# BeaglePhone_Rev1_SCH.net
KiCad netlist of a schematic drawn in Altium Designer
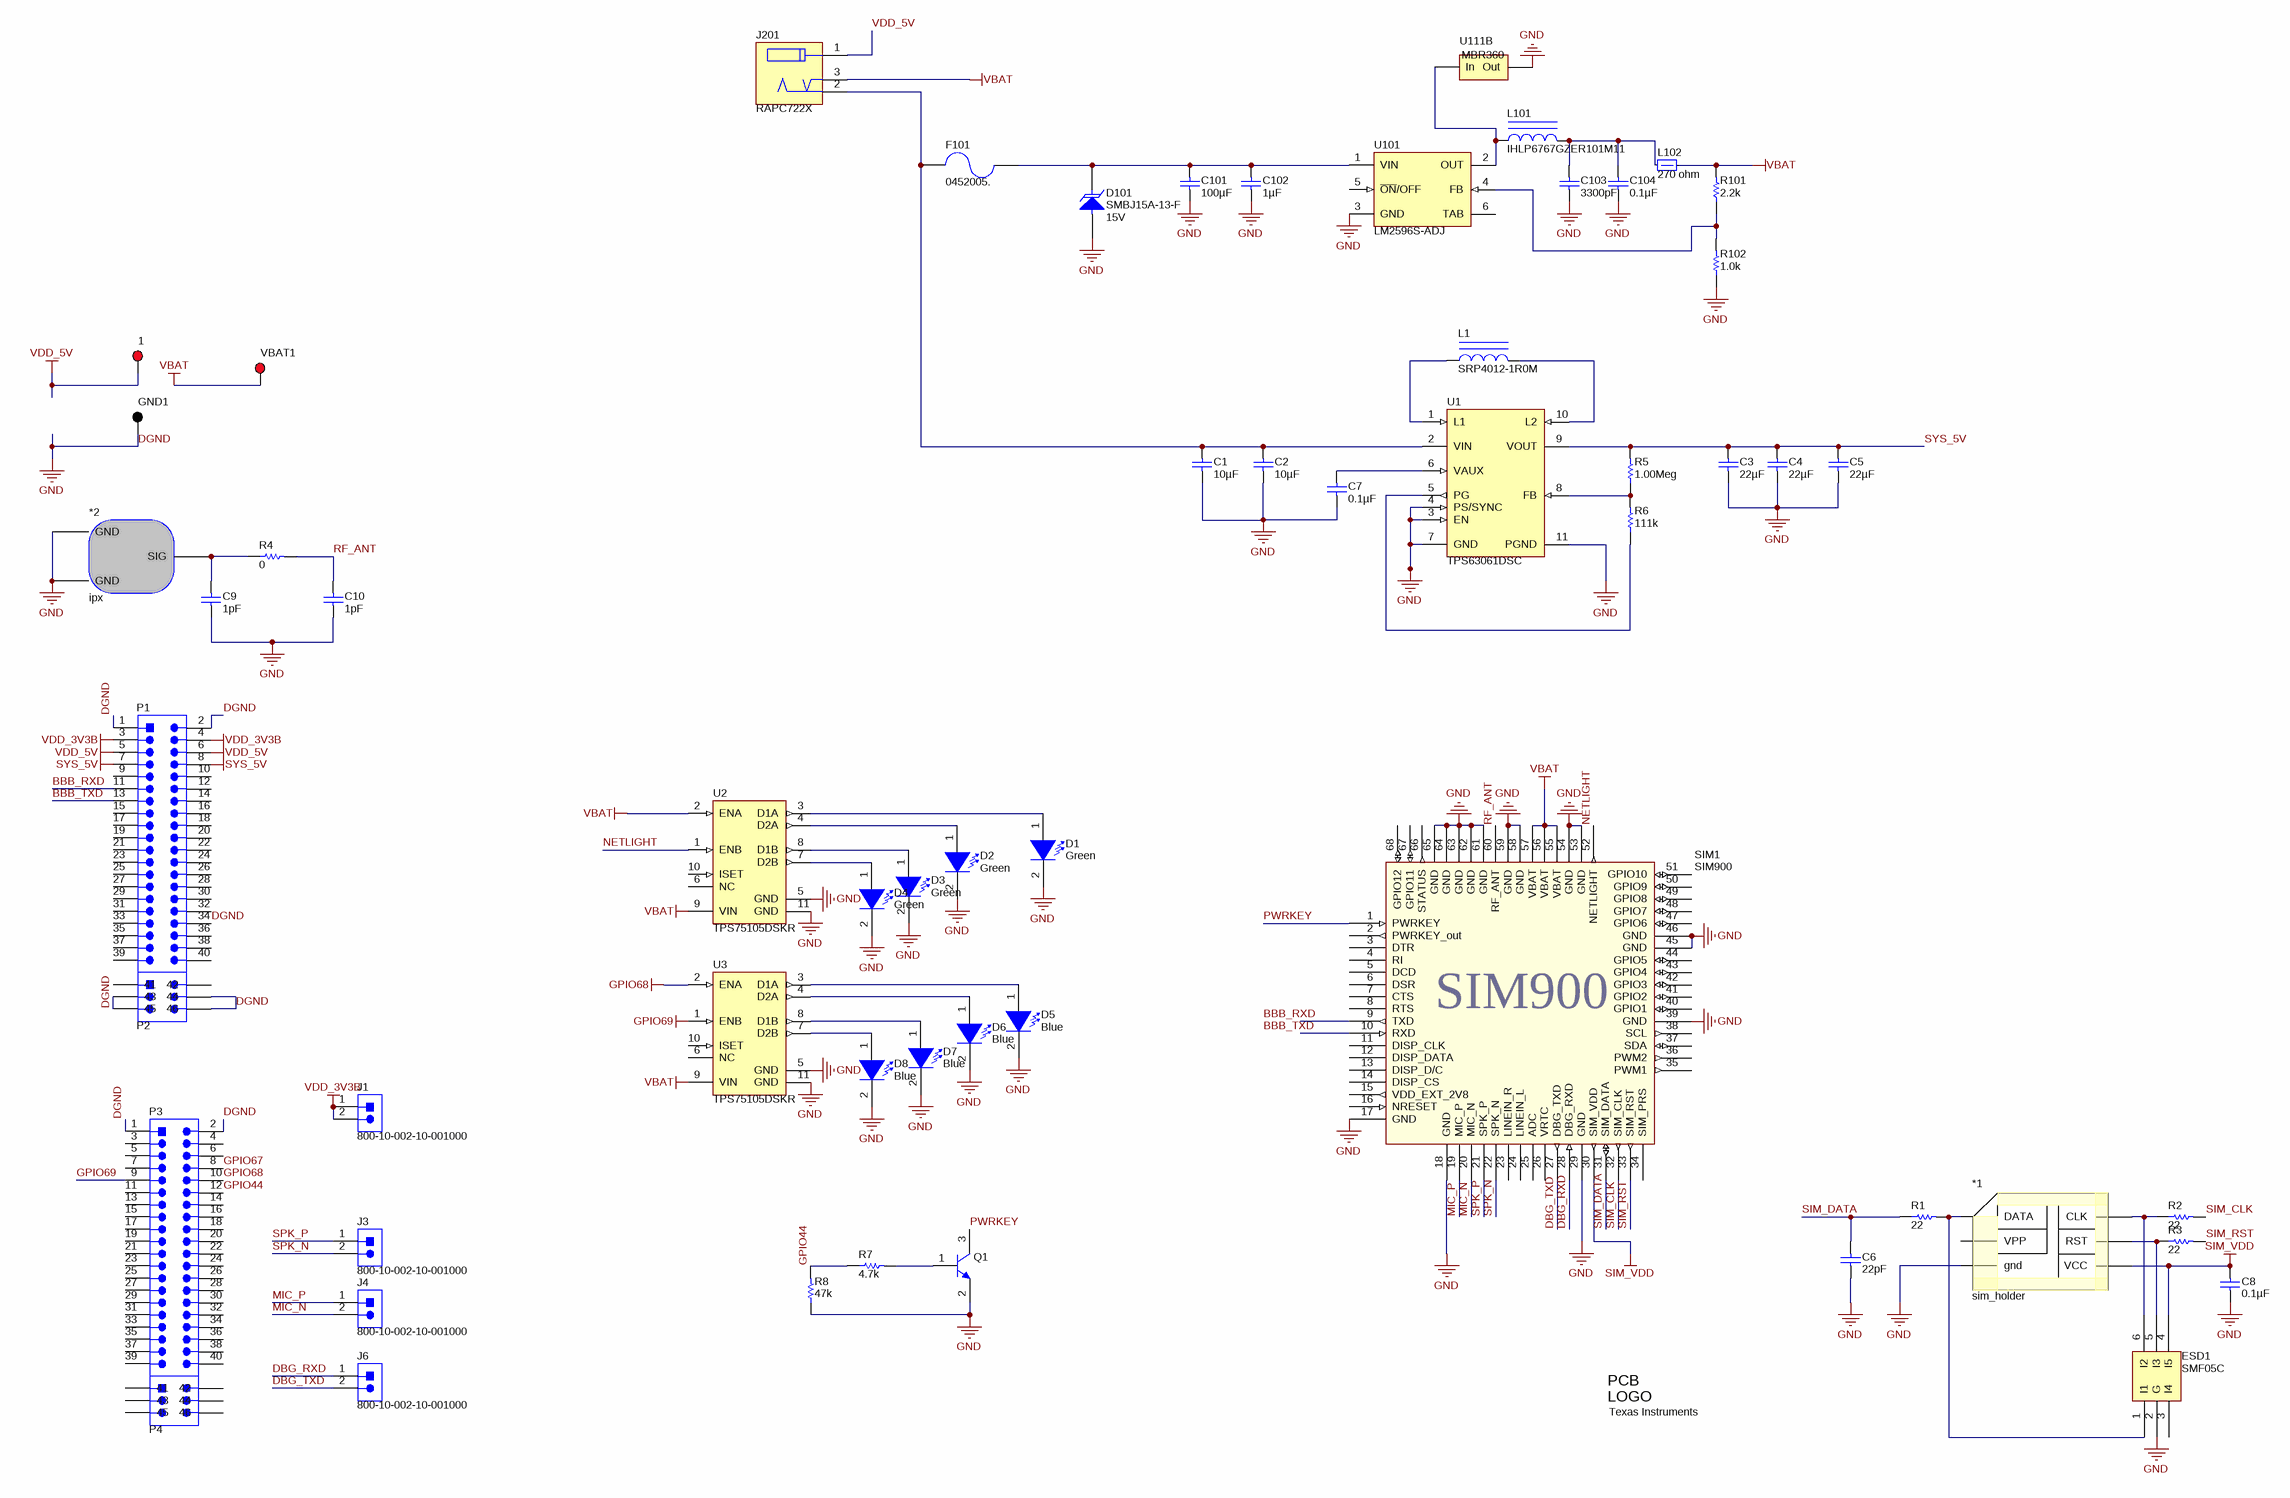
[diagram p0: BeaglePhone_Rev1_SCH.SchDoc]

(export (version "E")
  (design (tool "Eeschema 10.0.6"))
  (components
    (comp (ref "*1")
      (value "sim_holder")
      (footprint "SIM_socket")
      (libsource (lib "sim_holder") (part "sim_holder"))
    )
    (comp (ref "*2") (value "ipx") (footprint "IPX_U.FL") (libsource (lib "u.fl_IPX_connector") (part "ipx")))
    (comp (ref "1")
      (value "5005")
      (footprint "Keystone5005")
      (description "Test Point, TH, Compact, Red")
      (fields (field (name "MANUFACTURER") "Keystone") (field (name "DIGIKEYPARTNUMBER") "5005K-ND"))
      (libsource (lib "TemplateSCHLib") (part "5005"))
    )
    (comp (ref "C1")
      (value "C1608X5R1A106M")
      (footprint "0603")
      (description "CAP, CERM, 10uF, 10V, +/-20%, X5R, 0603")
      (fields (field (name "VALUEDISPLAYED") "10µF") (field (name "MANUFACTURER") "TDK"))
      (libsource (lib "Capacitor_Ceramic") (part "C1608X5R1A106M"))
    )
    (comp (ref "C2")
      (value "C1608X5R1A106M")
      (footprint "0603")
      (description "CAP, CERM, 10uF, 10V, +/-20%, X5R, 0603")
      (fields (field (name "VALUEDISPLAYED") "10µF") (field (name "MANUFACTURER") "TDK"))
      (libsource (lib "Capacitor_Ceramic") (part "C1608X5R1A106M"))
    )
    (comp (ref "C3")
      (value "C1608X5R0G226M080AA")
      (footprint "0603")
      (description "CAP, CERM, 22uF, 4V, +/-20%, X5R, 0603")
      (fields (field (name "VALUEDISPLAYED") "22µF") (field (name "MANUFACTURER") "TDK"))
      (libsource (lib "Capacitor_Ceramic") (part "C1608X5R0G226M080AA"))
    )
    (comp (ref "C4")
      (value "C1608X5R0G226M080AA")
      (footprint "0603")
      (description "CAP, CERM, 22uF, 4V, +/-20%, X5R, 0603")
      (fields (field (name "VALUEDISPLAYED") "22µF") (field (name "MANUFACTURER") "TDK"))
      (libsource (lib "Capacitor_Ceramic") (part "C1608X5R0G226M080AA"))
    )
    (comp (ref "C5")
      (value "C1608X5R0G226M080AA")
      (footprint "0603")
      (description "CAP, CERM, 22uF, 4V, +/-20%, X5R, 0603")
      (fields (field (name "VALUEDISPLAYED") "22µF") (field (name "MANUFACTURER") "TDK"))
      (libsource (lib "Capacitor_Ceramic") (part "C1608X5R0G226M080AA"))
    )
    (comp (ref "C6")
      (value "GRM1885C2A220JA01D")
      (footprint "0603")
      (description "CAP, CERM, 22pF, 100V, +/-5%, C0G/NP0, 0603")
      (fields (field (name "VALUEDISPLAYED") "22pF") (field (name "MANUFACTURER") "MuRata"))
      (libsource (lib "Capacitor_Ceramic") (part "GRM1885C2A220JA01D"))
    )
    (comp (ref "C7")
      (value "C0603X104K3RACTU")
      (footprint "0603")
      (description "CAP, CERM, 0.1uF, 25V, +/-10%, X7R, 0603")
      (fields (field (name "VALUEDISPLAYED") "0.1µF") (field (name "MANUFACTURER") "Kemet"))
      (libsource (lib "Capacitor_Ceramic") (part "C0603X104K3RACTU"))
    )
    (comp (ref "C8")
      (value "06035C104KAT2A")
      (footprint "0603")
      (description "CAP, CERM, 0.1 µF, 50 V, +/- 10%, X7R, 0603")
      (fields (field (name "VALUEDISPLAYED") "0.1µF") (field (name "MANUFACTURER") "AVX"))
      (libsource (lib "Capacitor_Ceramic") (part "06035C104KAT2A"))
    )
    (comp (ref "C9")
      (value "C0603C109C5GACTU")
      (footprint "0603")
      (description "CAP, CERM, 1pF, 50V, +/-25%, C0G/NP0, 0603")
      (fields (field (name "VALUEDISPLAYED") "1pF") (field (name "MANUFACTURER") "Kemet"))
      (libsource (lib "Capacitor_Ceramic") (part "C0603C109C5GACTU"))
    )
    (comp (ref "C10")
      (value "C0603C109C5GACTU")
      (footprint "0603")
      (description "CAP, CERM, 1pF, 50V, +/-25%, C0G/NP0, 0603")
      (fields (field (name "VALUEDISPLAYED") "1pF") (field (name "MANUFACTURER") "Kemet"))
      (libsource (lib "Capacitor_Ceramic") (part "C0603C109C5GACTU"))
    )
    (comp (ref "C101")
      (value "GRM31CR60J107ME39L")
      (footprint "1206")
      (description "CAP, CERM, 100uF, 6.3V, +/-20%, X5R, 1206")
      (fields (field (name "VALUEDISPLAYED") "100µF") (field (name "MANUFACTURER") "MuRata"))
      (libsource (lib "Capacitor_Ceramic") (part "GRM31CR60J107ME39L"))
    )
    (comp (ref "C102")
      (value "GRM188R61A105KA61D")
      (footprint "0603")
      (description "CAP, CERM, 1uF, 10V, +/-10%, X5R, 0603")
      (fields (field (name "VALUEDISPLAYED") "1µF") (field (name "MANUFACTURER") "MuRata"))
      (libsource (lib "Capacitor_Ceramic") (part "GRM188R61A105KA61D"))
    )
    (comp (ref "C103")
      (value "GRM188R71H332KA01D")
      (footprint "0603")
      (description "CAP, CERM, 3300pF, 50V, +/-10%, X7R, 0603")
      (fields (field (name "VALUEDISPLAYED") "3300pF") (field (name "MANUFACTURER") "MuRata"))
      (libsource (lib "Capacitor_Ceramic") (part "GRM188R71H332KA01D"))
    )
    (comp (ref "C104")
      (value "C0603X104K4RACTU")
      (footprint "0603")
      (description "CAP, CERM, 0.1uF, 16V, +/-10%, X7R, 0603")
      (fields (field (name "VALUEDISPLAYED") "0.1µF") (field (name "MANUFACTURER") "Kemet"))
      (libsource (lib "Capacitor_Ceramic") (part "C0603X104K4RACTU"))
    )
    (comp (ref "D1")
      (value "Green")
      (footprint "LG L29K_GREEN")
      (description "LED, Green, SMD")
      (fields (field (name "MANUFACTURER") "OSRAM") (field (name "PARTNUMBER") "LG L29K-G2J1-24-Z"))
      (libsource (lib "LED") (part "LG L29K-G2J1-24-Z"))
    )
    (comp (ref "D2")
      (value "Green")
      (footprint "LG L29K_GREEN")
      (description "LED, Green, SMD")
      (fields (field (name "MANUFACTURER") "OSRAM") (field (name "PARTNUMBER") "LG L29K-G2J1-24-Z"))
      (libsource (lib "LED") (part "LG L29K-G2J1-24-Z"))
    )
    (comp (ref "D3")
      (value "Green")
      (footprint "LG L29K_GREEN")
      (description "LED, Green, SMD")
      (fields (field (name "MANUFACTURER") "OSRAM") (field (name "PARTNUMBER") "LG L29K-G2J1-24-Z"))
      (libsource (lib "LED") (part "LG L29K-G2J1-24-Z"))
    )
    (comp (ref "D4")
      (value "Green")
      (footprint "LG L29K_GREEN")
      (description "LED, Green, SMD")
      (fields (field (name "MANUFACTURER") "OSRAM") (field (name "PARTNUMBER") "LG L29K-G2J1-24-Z"))
      (libsource (lib "LED") (part "LG L29K-G2J1-24-Z"))
    )
    (comp (ref "D5")
      (value "Blue")
      (footprint "LB Q39G_BLUE")
      (description "LED, Blue, SMD")
      (fields (field (name "MANUFACTURER") "OSRAM") (field (name "PARTNUMBER") "LB Q39G-L2N2-35-1"))
      (libsource (lib "LED") (part "LB Q39G-L2N2-35-1"))
    )
    (comp (ref "D6")
      (value "Blue")
      (footprint "LB Q39G_BLUE")
      (description "LED, Blue, SMD")
      (fields (field (name "MANUFACTURER") "OSRAM") (field (name "PARTNUMBER") "LB Q39G-L2N2-35-1"))
      (libsource (lib "LED") (part "LB Q39G-L2N2-35-1"))
    )
    (comp (ref "D7")
      (value "Blue")
      (footprint "LB Q39G_BLUE")
      (description "LED, Blue, SMD")
      (fields (field (name "MANUFACTURER") "OSRAM") (field (name "PARTNUMBER") "LB Q39G-L2N2-35-1"))
      (libsource (lib "LED") (part "LB Q39G-L2N2-35-1"))
    )
    (comp (ref "D8")
      (value "Blue")
      (footprint "LB Q39G_BLUE")
      (description "LED, Blue, SMD")
      (fields (field (name "MANUFACTURER") "OSRAM") (field (name "PARTNUMBER") "LB Q39G-L2N2-35-1"))
      (libsource (lib "LED") (part "LB Q39G-L2N2-35-1"))
    )
    (comp (ref "D101")
      (value "SMBJ15A-13-F")
      (footprint "SMB")
      (description "Diode, TVS, Uni, 15V, 600W, SMB")
      (fields (field (name "ALTIUM_VALUE") "15V") (field (name "MANUFACTURER") "Diodes Inc."))
      (libsource (lib "ZenerDiodes") (part "SMBJ15A-13-F"))
    )
    (comp (ref "ESD1") (value "SMF05C") (footprint "6pin") (libsource (lib "SMF05C") (part "SMF05C")))
    (comp (ref "F101")
      (value "0452005.")
      (footprint "SloBlo452")
      (description "Fuse, 5A, 125V, SMD")
      (fields (field (name "MANUFACTURER") "Littelfuse"))
      (libsource (lib "Fuse") (part "0452005."))
    )
    (comp (ref "GND1")
      (value "5006")
      (footprint "Keystone5006")
      (description "Test Point, TH, Compact, Black")
      (fields (field (name "MANUFACTURER") "Keystone") (field (name "DIGIKEYPARTNUMBER") "5006K-ND"))
      (libsource (lib "TemplateSCHLib") (part "5006"))
    )
    (comp (ref "J1")
      (value "800-10-002-10-001000")
      (footprint "Mill-Max_800-10-002-10-001000")
      (description "Header, 2x1, 100mil, SMT")
      (fields (field (name "MANUFACTURER") "Mill-Max"))
      (libsource (lib "Connectors") (part "800-10-002-10-001000"))
    )
    (comp (ref "J3")
      (value "800-10-002-10-001000")
      (footprint "Mill-Max_800-10-002-10-001000")
      (description "Header, 2x1, 100mil, SMT")
      (fields (field (name "MANUFACTURER") "Mill-Max"))
      (libsource (lib "Connectors") (part "800-10-002-10-001000"))
    )
    (comp (ref "J4")
      (value "800-10-002-10-001000")
      (footprint "Mill-Max_800-10-002-10-001000")
      (description "Header, 2x1, 100mil, SMT")
      (fields (field (name "MANUFACTURER") "Mill-Max"))
      (libsource (lib "Connectors") (part "800-10-002-10-001000"))
    )
    (comp (ref "J6")
      (value "800-10-002-10-001000")
      (footprint "Mill-Max_800-10-002-10-001000")
      (description "Header, 2x1, 100mil, SMT")
      (fields (field (name "MANUFACTURER") "Mill-Max"))
      (libsource (lib "Connectors") (part "800-10-002-10-001000"))
    )
    (comp (ref "J201")
      (value "RAPC722X")
      (footprint "CONN_RAPC722X")
      (description "Power Jack, mini, 2.1mm OD, R/A, TH")
      (fields (field (name "MANUFACTURER") "Switchcraft"))
      (libsource (lib "Connectors") (part "RAPC722X"))
    )
    (comp (ref "L1")
      (value "SRP4012-1R0M")
      (footprint "SRP4012")
      (description "Inductor, Flat Wire, Powdered Iron, 1uH, 4.8A, 0.0336 ohm, SMD")
      (fields (field (name "MANUFACTURER") "Bourns"))
      (libsource (lib "Inductor_Bourns") (part "SRP4012-1R0M"))
    )
    (comp (ref "L101")
      (value "IHLP6767GZER101M11")
      (footprint "IHLP-6767GZ-11")
      (description "Inductor, Shielded, Powdered Iron, 100uH, 4A, 0.11 ohm, SMD")
      (fields (field (name "MANUFACTURER") "Vishay-Dale"))
      (libsource (lib "Inductor_Vishay") (part "IHLP6767GZER101M11"))
    )
    (comp (ref "L102")
      (value "270 ohm")
      (footprint "2220")
      (description "Ferrite Bead, 270 ohm @ 100MHz, 4A, 2220")
      (fields
        (field (name "PARTNUMBER") "HI2220P271R-10")
        (field (name "MANUFACTURER") "Laird-Signal Integrity Products")
      )
      (libsource (lib "FerriteBead") (part "HI2220P271R-10"))
    )
    (comp (ref "Logo1")
      (value "Texas Instruments")
      (footprint "TI_Symbol_Overlay_Small")
      (description "Texas Instrument Corporate Signature")
      (libsource (lib "Logos") (part "TI_Logo"))
    )
    (comp (ref "P1")
      (value "Comment")
      (footprint "TSW-120-07-G-D")
      (description "Header, 100mil, 20x2, Gold, TH")
      (fields (field (name "PARTNUMBER") "TSW-120-07-G-D") (field (name "MANUFACTURER") "Samtec"))
      (libsource (lib "Connectors") (part "TSW-120-07-G-D"))
    )
    (comp (ref "P2")
      (value "Comment")
      (footprint "SULLINS_PEC03DAAN")
      (description "Header, 100mil, 3x2, Tin, TH")
      (fields
        (field (name "PARTNUMBER") "PEC03DAAN")
        (field (name "MANUFACTURER") "Sullins Connector Solutions")
      )
      (libsource (lib "Connectors") (part "PEC03DAAN"))
    )
    (comp (ref "P3")
      (value "Comment")
      (footprint "TSW-120-07-G-D")
      (description "Header, 100mil, 20x2, Gold, TH")
      (fields (field (name "PARTNUMBER") "TSW-120-07-G-D") (field (name "MANUFACTURER") "Samtec"))
      (libsource (lib "Connectors") (part "TSW-120-07-G-D"))
    )
    (comp (ref "P4")
      (value "Comment")
      (footprint "SULLINS_PEC03DAAN")
      (description "Header, 100mil, 3x2, Tin, TH")
      (fields
        (field (name "PARTNUMBER") "PEC03DAAN")
        (field (name "MANUFACTURER") "Sullins Connector Solutions")
      )
      (libsource (lib "Connectors") (part "PEC03DAAN"))
    )
    (comp (ref "Q1")
      (value "MMBT2222LT1G")
      (footprint "SOT-23")
      (description "Transistor, NPN, 30V, 0.6A, SOT-23")
      (fields (field (name "MANUFACTURER") "ON Semiconductor"))
      (libsource (lib "Bipolar_Transistor") (part "MMBT2222LT1G, ON Semiconductor"))
    )
    (comp (ref "R1")
      (value "22")
      (footprint "0603")
      (description "RES, 22 ohm, 5%, 0.1W, 0603")
      (fields (field (name "PARTNUMBER") "CRCW060322R0JNEA") (field (name "MANUFACTURER") "Vishay-Dale"))
      (libsource (lib "Resistor_0603") (part "CRCW060322R0JNEA"))
    )
    (comp (ref "R2")
      (value "22")
      (footprint "0603")
      (description "RES, 22 ohm, 5%, 0.1W, 0603")
      (fields (field (name "PARTNUMBER") "CRCW060322R0JNEA") (field (name "MANUFACTURER") "Vishay-Dale"))
      (libsource (lib "Resistor_0603") (part "CRCW060322R0JNEA"))
    )
    (comp (ref "R3")
      (value "22")
      (footprint "0603")
      (description "RES, 22 ohm, 5%, 0.1W, 0603")
      (fields (field (name "PARTNUMBER") "CRCW060322R0JNEA") (field (name "MANUFACTURER") "Vishay-Dale"))
      (libsource (lib "Resistor_0603") (part "CRCW060322R0JNEA"))
    )
    (comp (ref "R4")
      (value "0")
      (footprint "0805_HV")
      (description "RES, 0 ohm, 5%, 0.333W, 0805")
      (fields (field (name "PARTNUMBER") "CRCW08050000Z0EAHP") (field (name "MANUFACTURER") "Vishay-Dale"))
      (libsource (lib "Resistor_0805") (part "CRCW08050000Z0EAHP"))
    )
    (comp (ref "R5")
      (value "1.00Meg")
      (footprint "0603")
      (description "RES, 1.00Meg ohm, 1%, 0.1W, 0603")
      (fields (field (name "PARTNUMBER") "CRCW06031M00FKEA") (field (name "MANUFACTURER") "Vishay-Dale"))
      (libsource (lib "Resistor_0603") (part "CRCW06031M00FKEA"))
    )
    (comp (ref "R6")
      (value "111k")
      (footprint "0603")
      (description "RES, 111k ohm, 0.1%, 0.1W, 0603")
      (fields (field (name "PARTNUMBER") "RT0603BRD07111KL") (field (name "MANUFACTURER") "Yageo America"))
      (libsource (lib "Resistor_0603") (part "RT0603BRD07111KL"))
    )
    (comp (ref "R7")
      (value "CRCW04024K70JNED")
      (footprint "0402")
      (description "RES, 4.7 k, 5%, 0.063 W, 0402")
      (fields (field (name "VALUEDISPLAYED") "4.7k") (field (name "MANUFACTURER") "Vishay-Dale"))
      (libsource (lib "Resistor_0402") (part "CRCW04024K70JNED"))
    )
    (comp (ref "R8")
      (value "CRCW04024K70JNED")
      (footprint "0402")
      (description "RES, 4.7 k, 5%, 0.063 W, 0402")
      (fields (field (name "VALUEDISPLAYED") "47k") (field (name "MANUFACTURER") "Vishay-Dale"))
      (libsource (lib "Resistor_0402") (part "CRCW04024K70JNED"))
    )
    (comp (ref "R101")
      (value "2.2k")
      (footprint "0603")
      (description "RES, 2.2k ohm, 5%, 0.1W, 0603")
      (fields (field (name "PARTNUMBER") "CRCW06032K20JNEA") (field (name "MANUFACTURER") "Vishay-Dale"))
      (libsource (lib "Resistor_0603") (part "CRCW06032K20JNEA"))
    )
    (comp (ref "R102")
      (value "1.0k")
      (footprint "0603")
      (description "RES, 1.0k ohm, 5%, 0.1W, 0603")
      (fields (field (name "PARTNUMBER") "CRCW06031K00JNEA") (field (name "MANUFACTURER") "Vishay-Dale"))
      (libsource (lib "Resistor_0603") (part "CRCW06031K00JNEA"))
    )
    (comp (ref "SIM1")
      (value "SIM900")
      (footprint "PCBComponent_1 - duplicate1")
      (libsource (lib "Schematic Components") (part "SIM900"))
    )
    (comp (ref "U1")
      (value "TPS63061DSC")
      (footprint "DSC0010E")
      (description "HIGH INPUT VOLTAGE BUCK-BOOST CONVERTER WITH 2A SWITCH CURRENT, DSC0010E")
      (fields (field (name "MANUFACTURER") "Texas Instruments"))
      (libsource (lib "TI_Pre_Release") (part "TPS63061DSC"))
    )
    (comp (ref "U2")
      (value "TPS75105DSKR")
      (footprint "DSK0010A")
      (fields
        (field (name "MANUFACTURER") "Texas Instruments")
        (field (name "ALTERNATE PARTNUMBER") "Equivalent")
      )
      (libsource (lib "TI Power Management Lighting and Display") (part "TPS75105DSKR"))
    )
    (comp (ref "U3")
      (value "TPS75105DSKR")
      (footprint "DSK0010A")
      (fields
        (field (name "MANUFACTURER") "Texas Instruments")
        (field (name "ALTERNATE PARTNUMBER") "Equivalent")
      )
      (libsource (lib "TI Power Management Lighting and Display") (part "TPS75105DSKR"))
    )
    (comp (ref "U101")
      (value "LM2596S-ADJ")
      (footprint "TS5B_N")
      (description "SIMPLE SWITCHER® Power Converter 150 KHz 3A Step-Down Voltage Regulator, 5-pin TO-263")
      (fields (field (name "MANUFACTURER") "National Semiconductor"))
      (libsource (lib "NSC Switcher") (part "LM2596S-ADJ"))
    )
    (comp (ref "U111")
      (value "Used in BOM report")
      (footprint "PCBComponent_1 - duplicate2")
      (libsource (lib "josh") (part "MBR360"))
    )
    (comp (ref "VBAT1")
      (value "5005")
      (footprint "Keystone5005")
      (description "Test Point, TH, Compact, Red")
      (fields (field (name "MANUFACTURER") "Keystone") (field (name "DIGIKEYPARTNUMBER") "5005K-ND"))
      (libsource (lib "TemplateSCHLib") (part "5005"))
    )
  )
  (nets
    (net (code "2") (name "/BBB_RXD") (class "Default")
      (node (ref "P1") (pin "11") (pinfunction "11_11") (pintype "passive"))
    )
    (net (code "3") (name "/BBB_TXD") (class "Default")
      (node (ref "P1") (pin "13") (pinfunction "13_13") (pintype "passive"))
    )
    (net (code "4") (name "/DBG_RXD") (class "Default")
      (node (ref "J6") (pin "1") (pinfunction "1_1") (pintype "passive"))
      (node (ref "SIM1") (pin "28") (pinfunction "DBG_RXD_28") (pintype "input"))
    )
    (net (code "5") (name "/DBG_TXD") (class "Default")
      (node (ref "J6") (pin "2") (pinfunction "2_2") (pintype "passive"))
      (node (ref "SIM1") (pin "27") (pinfunction "DBG_TXD_27") (pintype "output"))
    )
    (net (code "6") (name "/GPIO44") (class "Default")
      (node (ref "P3") (pin "12") (pinfunction "12_12") (pintype "passive"))
      (node (ref "R7") (pin "1") (pinfunction "1_1") (pintype "passive"))
      (node (ref "R8") (pin "2") (pinfunction "2_2") (pintype "passive"))
    )
    (net (code "7") (name "/GPIO67") (class "Default")
      (node (ref "P3") (pin "8") (pinfunction "8_8") (pintype "passive"))
    )
    (net (code "8") (name "/MIC_N") (class "Default")
      (node (ref "J4") (pin "2") (pinfunction "2_2") (pintype "passive"))
      (node (ref "SIM1") (pin "20") (pinfunction "MIC_N_20") (pintype "passive"))
    )
    (net (code "9") (name "/MIC_P") (class "Default")
      (node (ref "J4") (pin "1") (pinfunction "1_1") (pintype "passive"))
      (node (ref "SIM1") (pin "19") (pinfunction "MIC_P_19") (pintype "passive"))
    )
    (net (code "10") (name "/NETLIGHT") (class "Default")
      (node (ref "SIM1") (pin "52") (pinfunction "NETLIGHT_52") (pintype "output"))
      (node (ref "U2") (pin "1") (pinfunction "ENB_1") (pintype "input"))
    )
    (net (code "11") (name "/PWRKEY") (class "Default")
      (node (ref "Q1") (pin "3") (pinfunction "C_3") (pintype "passive"))
      (node (ref "SIM1") (pin "1") (pinfunction "PWRKEY_1") (pintype "input"))
    )
    (net (code "12") (name "/RF_ANT") (class "Default")
      (node (ref "C10") (pin "1") (pinfunction "1_1") (pintype "passive"))
      (node (ref "R4") (pin "2") (pinfunction "2_2") (pintype "passive"))
      (node (ref "SIM1") (pin "60") (pinfunction "RF_ANT_60") (pintype "passive"))
    )
    (net (code "13") (name "/SIM_CLK") (class "Default")
      (node (ref "R2") (pin "2") (pinfunction "2_2") (pintype "passive"))
      (node (ref "SIM1") (pin "32") (pinfunction "SIM_CLK_32") (pintype "output"))
    )
    (net (code "14") (name "/SIM_DATA") (class "Default")
      (node (ref "C6") (pin "1") (pinfunction "1_1") (pintype "passive"))
      (node (ref "R1") (pin "1") (pinfunction "1_1") (pintype "passive"))
      (node (ref "SIM1") (pin "31") (pinfunction "SIM_DATA_31") (pintype "bidirectional"))
    )
    (net (code "15") (name "/SIM_RST") (class "Default")
      (node (ref "R3") (pin "2") (pinfunction "2_2") (pintype "passive"))
      (node (ref "SIM1") (pin "33") (pinfunction "SIM_RST_33") (pintype "output"))
    )
    (net (code "16") (name "/SPK_N") (class "Default")
      (node (ref "J3") (pin "2") (pinfunction "2_2") (pintype "passive"))
      (node (ref "SIM1") (pin "22") (pinfunction "SPK_N_22") (pintype "passive"))
    )
    (net (code "17") (name "/SPK_P") (class "Default")
      (node (ref "J3") (pin "1") (pinfunction "1_1") (pintype "passive"))
      (node (ref "SIM1") (pin "21") (pinfunction "SPK_P_21") (pintype "passive"))
    )
    (net (code "18") (name "GND") (class "Default")
      (node (ref "*1") (pin "1") (pinfunction "gnd_1") (pintype "passive"))
      (node (ref "*2") (pin "1") (pinfunction "GND_1") (pintype "passive"))
      (node (ref "*2") (pin "2") (pinfunction "GND_2") (pintype "passive"))
      (node (ref "C1") (pin "1") (pinfunction "1_1") (pintype "passive"))
      (node (ref "C10") (pin "2") (pinfunction "2_2") (pintype "passive"))
      (node (ref "C101") (pin "2") (pinfunction "2_2") (pintype "passive"))
      (node (ref "C102") (pin "2") (pinfunction "2_2") (pintype "passive"))
      (node (ref "C103") (pin "2") (pinfunction "2_2") (pintype "passive"))
      (node (ref "C104") (pin "2") (pinfunction "2_2") (pintype "passive"))
      (node (ref "C2") (pin "1") (pinfunction "1_1") (pintype "passive"))
      (node (ref "C3") (pin "1") (pinfunction "1_1") (pintype "passive"))
      (node (ref "C4") (pin "1") (pinfunction "1_1") (pintype "passive"))
      (node (ref "C5") (pin "1") (pinfunction "1_1") (pintype "passive"))
      (node (ref "C6") (pin "2") (pinfunction "2_2") (pintype "passive"))
      (node (ref "C7") (pin "2") (pinfunction "2_2") (pintype "passive"))
      (node (ref "C8") (pin "2") (pinfunction "2_2") (pintype "passive"))
      (node (ref "C9") (pin "2") (pinfunction "2_2") (pintype "passive"))
      (node (ref "D1") (pin "2") (pinfunction "K_2") (pintype "passive"))
      (node (ref "D101") (pin "2") (pinfunction "A_2") (pintype "passive"))
      (node (ref "D2") (pin "2") (pinfunction "K_2") (pintype "passive"))
      (node (ref "D3") (pin "2") (pinfunction "K_2") (pintype "passive"))
      (node (ref "D4") (pin "2") (pinfunction "K_2") (pintype "passive"))
      (node (ref "D5") (pin "2") (pinfunction "K_2") (pintype "passive"))
      (node (ref "D6") (pin "2") (pinfunction "K_2") (pintype "passive"))
      (node (ref "D7") (pin "2") (pinfunction "K_2") (pintype "passive"))
      (node (ref "D8") (pin "2") (pinfunction "K_2") (pintype "passive"))
      (node (ref "ESD1") (pin "2") (pinfunction "G_2") (pintype "passive"))
      (node (ref "GND1") (pin "1") (pintype "passive"))
      (node (ref "P1") (pin "1") (pinfunction "1_1") (pintype "passive"))
      (node (ref "P1") (pin "2") (pinfunction "2_2") (pintype "passive"))
      (node (ref "P1") (pin "34") (pinfunction "34_34") (pintype "passive"))
      (node (ref "P2") (pin "3") (pinfunction "43_3") (pintype "passive"))
      (node (ref "P2") (pin "4") (pinfunction "44_4") (pintype "passive"))
      (node (ref "P2") (pin "5") (pinfunction "45_5") (pintype "passive"))
      (node (ref "P2") (pin "6") (pinfunction "46_6") (pintype "passive"))
      (node (ref "P3") (pin "1") (pinfunction "1_1") (pintype "passive"))
      (node (ref "P3") (pin "2") (pinfunction "2_2") (pintype "passive"))
      (node (ref "Q1") (pin "2") (pinfunction "E_2") (pintype "passive"))
      (node (ref "R102") (pin "1") (pinfunction "1_1") (pintype "passive"))
      (node (ref "R8") (pin "1") (pinfunction "1_1") (pintype "passive"))
      (node (ref "SIM1") (pin "17") (pinfunction "GND_17") (pintype "passive"))
      (node (ref "SIM1") (pin "18") (pinfunction "GND_18") (pintype "passive"))
      (node (ref "SIM1") (pin "29") (pinfunction "GND_29") (pintype "passive"))
      (node (ref "SIM1") (pin "39") (pinfunction "GND_39") (pintype "passive"))
      (node (ref "SIM1") (pin "45") (pinfunction "GND_45") (pintype "passive"))
      (node (ref "SIM1") (pin "46") (pinfunction "GND_46") (pintype "passive"))
      (node (ref "SIM1") (pin "53") (pinfunction "GND_53") (pintype "passive"))
      (node (ref "SIM1") (pin "54") (pinfunction "GND_54") (pintype "passive"))
      (node (ref "SIM1") (pin "58") (pinfunction "GND_58") (pintype "passive"))
      (node (ref "SIM1") (pin "59") (pinfunction "GND_59") (pintype "passive"))
      (node (ref "SIM1") (pin "61") (pinfunction "GND_61") (pintype "passive"))
      (node (ref "SIM1") (pin "62") (pinfunction "GND_62") (pintype "passive"))
      (node (ref "SIM1") (pin "63") (pinfunction "GND_63") (pintype "passive"))
      (node (ref "SIM1") (pin "64") (pinfunction "GND_64") (pintype "passive"))
      (node (ref "SIM1") (pin "65") (pinfunction "GND_65") (pintype "passive"))
      (node (ref "U1") (pin "11") (pinfunction "PGND_11") (pintype "power_in"))
      (node (ref "U1") (pin "3") (pinfunction "EN_3") (pintype "input"))
      (node (ref "U1") (pin "4") (pinfunction "PS/SYNC_4") (pintype "input"))
      (node (ref "U1") (pin "7") (pinfunction "GND_7") (pintype "power_in"))
      (node (ref "U101") (pin "3") (pinfunction "GND_3") (pintype "power_in"))
      (node (ref "U111") (pin "2") (pinfunction "Out_2") (pintype "passive"))
      (node (ref "U2") (pin "11") (pinfunction "GND_11") (pintype "power_in"))
      (node (ref "U2") (pin "5") (pinfunction "GND_5") (pintype "power_in"))
      (node (ref "U3") (pin "11") (pinfunction "GND_11") (pintype "power_in"))
      (node (ref "U3") (pin "5") (pinfunction "GND_5") (pintype "power_in"))
    )
    (net (code "19") (name "GPIO68") (class "Default")
      (node (ref "P3") (pin "10") (pinfunction "10_10") (pintype "passive"))
      (node (ref "U3") (pin "2") (pinfunction "ENA_2") (pintype "input"))
    )
    (net (code "20") (name "GPIO69") (class "Default")
      (node (ref "P3") (pin "9") (pinfunction "9_9") (pintype "passive"))
      (node (ref "U3") (pin "1") (pinfunction "ENB_1") (pintype "input"))
    )
    (net (code "21") (name "Net-(*1-CLK)") (class "Default")
      (node (ref "*1") (pin "4") (pinfunction "CLK_4") (pintype "passive"))
      (node (ref "ESD1") (pin "6") (pinfunction "I2_6") (pintype "passive"))
      (node (ref "R2") (pin "1") (pinfunction "1_1") (pintype "passive"))
    )
    (net (code "22") (name "Net-(*1-DATA)") (class "Default")
      (node (ref "*1") (pin "3") (pinfunction "DATA_3") (pintype "passive"))
      (node (ref "ESD1") (pin "1") (pinfunction "I1_1") (pintype "passive"))
      (node (ref "R1") (pin "2") (pinfunction "2_2") (pintype "passive"))
    )
    (net (code "23") (name "Net-(*1-RST)") (class "Default")
      (node (ref "*1") (pin "5") (pinfunction "RST_5") (pintype "passive"))
      (node (ref "ESD1") (pin "5") (pinfunction "I3_5") (pintype "passive"))
      (node (ref "R3") (pin "1") (pinfunction "1_1") (pintype "passive"))
    )
    (net (code "24") (name "Net-(*2-SIG)") (class "Default")
      (node (ref "*2") (pin "3") (pinfunction "SIG_3") (pintype "passive"))
      (node (ref "C9") (pin "1") (pinfunction "1_1") (pintype "passive"))
      (node (ref "R4") (pin "1") (pinfunction "1_1") (pintype "passive"))
    )
    (net (code "25") (name "Net-(C103-Pad1)") (class "Default")
      (node (ref "C103") (pin "1") (pinfunction "1_1") (pintype "passive"))
      (node (ref "C104") (pin "1") (pinfunction "1_1") (pintype "passive"))
      (node (ref "L101") (pin "2") (pinfunction "2_2") (pintype "passive"))
      (node (ref "L102") (pin "1") (pinfunction "1_1") (pintype "passive"))
    )
    (net (code "26") (name "Net-(D1-A)") (class "Default")
      (node (ref "D1") (pin "1") (pinfunction "A_1") (pintype "passive"))
      (node (ref "U2") (pin "3") (pinfunction "D1A_3") (pintype "output"))
    )
    (net (code "27") (name "Net-(D2-A)") (class "Default")
      (node (ref "D2") (pin "1") (pinfunction "A_1") (pintype "passive"))
      (node (ref "U2") (pin "4") (pinfunction "D2A_4") (pintype "output"))
    )
    (net (code "28") (name "Net-(D3-A)") (class "Default")
      (node (ref "D3") (pin "1") (pinfunction "A_1") (pintype "passive"))
      (node (ref "U2") (pin "8") (pinfunction "D1B_8") (pintype "output"))
    )
    (net (code "29") (name "Net-(D4-A)") (class "Default")
      (node (ref "D4") (pin "1") (pinfunction "A_1") (pintype "passive"))
      (node (ref "U2") (pin "7") (pinfunction "D2B_7") (pintype "output"))
    )
    (net (code "30") (name "Net-(D5-A)") (class "Default")
      (node (ref "D5") (pin "1") (pinfunction "A_1") (pintype "passive"))
      (node (ref "U3") (pin "3") (pinfunction "D1A_3") (pintype "output"))
    )
    (net (code "31") (name "Net-(D6-A)") (class "Default")
      (node (ref "D6") (pin "1") (pinfunction "A_1") (pintype "passive"))
      (node (ref "U3") (pin "4") (pinfunction "D2A_4") (pintype "output"))
    )
    (net (code "32") (name "Net-(D7-A)") (class "Default")
      (node (ref "D7") (pin "1") (pinfunction "A_1") (pintype "passive"))
      (node (ref "U3") (pin "8") (pinfunction "D1B_8") (pintype "output"))
    )
    (net (code "33") (name "Net-(D8-A)") (class "Default")
      (node (ref "D8") (pin "1") (pinfunction "A_1") (pintype "passive"))
      (node (ref "U3") (pin "7") (pinfunction "D2B_7") (pintype "output"))
    )
    (net (code "34") (name "Net-(D101-K)") (class "Default")
      (node (ref "C101") (pin "1") (pinfunction "1_1") (pintype "passive"))
      (node (ref "C102") (pin "1") (pinfunction "1_1") (pintype "passive"))
      (node (ref "D101") (pin "1") (pinfunction "K_1") (pintype "passive"))
      (node (ref "F101") (pin "1") (pinfunction "1_1") (pintype "passive"))
      (node (ref "U101") (pin "1") (pinfunction "VIN_1") (pintype "power_in"))
    )
    (net (code "35") (name "Net-(Q1-B)") (class "Default")
      (node (ref "Q1") (pin "1") (pinfunction "B_1") (pintype "passive"))
      (node (ref "R7") (pin "2") (pinfunction "2_2") (pintype "passive"))
    )
    (net (code "36") (name "Net-(U1-FB)") (class "Default")
      (node (ref "R5") (pin "1") (pinfunction "1_1") (pintype "passive"))
      (node (ref "R6") (pin "2") (pinfunction "2_2") (pintype "passive"))
      (node (ref "U1") (pin "8") (pinfunction "FB_8") (pintype "input"))
    )
    (net (code "37") (name "Net-(U1-L1)") (class "Default")
      (node (ref "L1") (pin "1") (pinfunction "1_1") (pintype "passive"))
      (node (ref "U1") (pin "1") (pinfunction "L1_1") (pintype "input"))
    )
    (net (code "38") (name "Net-(U1-L2)") (class "Default")
      (node (ref "L1") (pin "2") (pinfunction "2_2") (pintype "passive"))
      (node (ref "U1") (pin "10") (pinfunction "L2_10") (pintype "input"))
    )
    (net (code "39") (name "Net-(U1-PG)") (class "Default")
      (node (ref "R6") (pin "1") (pinfunction "1_1") (pintype "passive"))
      (node (ref "U1") (pin "5") (pinfunction "PG_5") (pintype "output"))
    )
    (net (code "40") (name "Net-(U1-VAUX)") (class "Default")
      (node (ref "C7") (pin "1") (pinfunction "1_1") (pintype "passive"))
      (node (ref "U1") (pin "6") (pinfunction "VAUX_6") (pintype "input"))
    )
    (net (code "41") (name "Net-(U1-VIN)") (class "Default")
      (node (ref "C1") (pin "2") (pinfunction "2_2") (pintype "passive"))
      (node (ref "C2") (pin "2") (pinfunction "2_2") (pintype "passive"))
      (node (ref "F101") (pin "2") (pinfunction "2_2") (pintype "passive"))
      (node (ref "J201") (pin "2") (pinfunction "2_2") (pintype "passive"))
      (node (ref "U1") (pin "2") (pinfunction "VIN_2") (pintype "power_in"))
    )
    (net (code "42") (name "Net-(U101-FB)") (class "Default")
      (node (ref "R101") (pin "1") (pinfunction "1_1") (pintype "passive"))
      (node (ref "R102") (pin "2") (pinfunction "2_2") (pintype "passive"))
      (node (ref "U101") (pin "4") (pinfunction "FB_4") (pintype "input"))
    )
    (net (code "43") (name "Net-(U101-OUT)") (class "Default")
      (node (ref "L101") (pin "1") (pinfunction "1_1") (pintype "passive"))
      (node (ref "U101") (pin "2") (pinfunction "OUT_2") (pintype "power_in"))
      (node (ref "U111") (pin "1") (pinfunction "In_1") (pintype "passive"))
    )
    (net (code "44") (name "SIM_VDD") (class "Default")
      (node (ref "*1") (pin "6") (pinfunction "VCC_6") (pintype "passive"))
      (node (ref "C8") (pin "1") (pinfunction "1_1") (pintype "passive"))
      (node (ref "ESD1") (pin "4") (pinfunction "I5_4") (pintype "passive"))
      (node (ref "SIM1") (pin "30") (pinfunction "SIM_VDD_30") (pintype "output"))
    )
    (net (code "45") (name "SYS_5V") (class "Default")
      (node (ref "C3") (pin "2") (pinfunction "2_2") (pintype "passive"))
      (node (ref "C4") (pin "2") (pinfunction "2_2") (pintype "passive"))
      (node (ref "C5") (pin "2") (pinfunction "2_2") (pintype "passive"))
      (node (ref "P1") (pin "7") (pinfunction "7_7") (pintype "passive"))
      (node (ref "P1") (pin "8") (pinfunction "8_8") (pintype "passive"))
      (node (ref "R5") (pin "2") (pinfunction "2_2") (pintype "passive"))
      (node (ref "U1") (pin "9") (pinfunction "VOUT_9") (pintype "power_in"))
    )
    (net (code "46") (name "VBAT") (class "Default")
      (node (ref "J201") (pin "3") (pinfunction "3_3") (pintype "passive"))
      (node (ref "L102") (pin "2") (pinfunction "2_2") (pintype "passive"))
      (node (ref "R101") (pin "2") (pinfunction "2_2") (pintype "passive"))
      (node (ref "SIM1") (pin "55") (pinfunction "VBAT_55") (pintype "power_in"))
      (node (ref "SIM1") (pin "56") (pinfunction "VBAT_56") (pintype "power_in"))
      (node (ref "SIM1") (pin "57") (pinfunction "VBAT_57") (pintype "power_in"))
      (node (ref "U2") (pin "2") (pinfunction "ENA_2") (pintype "input"))
      (node (ref "U2") (pin "9") (pinfunction "VIN_9") (pintype "power_in"))
      (node (ref "U3") (pin "9") (pinfunction "VIN_9") (pintype "power_in"))
      (node (ref "VBAT1") (pin "1") (pintype "passive"))
    )
    (net (code "47") (name "VDD_3V3B") (class "Default")
      (node (ref "J1") (pin "1") (pinfunction "1_1") (pintype "passive"))
      (node (ref "J1") (pin "2") (pinfunction "2_2") (pintype "passive"))
      (node (ref "P1") (pin "3") (pinfunction "3_3") (pintype "passive"))
      (node (ref "P1") (pin "4") (pinfunction "4_4") (pintype "passive"))
    )
    (net (code "48") (name "VDD_5V") (class "Default")
      (node (ref "1") (pin "1") (pintype "passive"))
      (node (ref "J201") (pin "1") (pinfunction "1_1") (pintype "passive"))
      (node (ref "P1") (pin "5") (pinfunction "5_5") (pintype "passive"))
      (node (ref "P1") (pin "6") (pinfunction "6_6") (pintype "passive"))
    )
    (net (code "49") (name "unconnected-(*1-VPP-Pad2)") (class "Default")
      (node (ref "*1") (pin "2") (pinfunction "VPP_2") (pintype "passive"))
    )
    (net (code "50") (name "unconnected-(ESD1-I4-Pad3)") (class "Default")
      (node (ref "ESD1") (pin "3") (pinfunction "I4_3") (pintype "passive"))
    )
    (net (code "51") (name "unconnected-(P1-Pad9)") (class "Default")
      (node (ref "P1") (pin "9") (pinfunction "9_9") (pintype "passive"))
    )
    (net (code "52") (name "unconnected-(P1-Pad10)") (class "Default")
      (node (ref "P1") (pin "10") (pinfunction "10_10") (pintype "passive"))
    )
    (net (code "53") (name "unconnected-(P1-Pad12)") (class "Default")
      (node (ref "P1") (pin "12") (pinfunction "12_12") (pintype "passive"))
    )
    (net (code "54") (name "unconnected-(P1-Pad14)") (class "Default")
      (node (ref "P1") (pin "14") (pinfunction "14_14") (pintype "passive"))
    )
    (net (code "55") (name "unconnected-(P1-Pad15)") (class "Default")
      (node (ref "P1") (pin "15") (pinfunction "15_15") (pintype "passive"))
    )
    (net (code "56") (name "unconnected-(P1-Pad16)") (class "Default")
      (node (ref "P1") (pin "16") (pinfunction "16_16") (pintype "passive"))
    )
    (net (code "57") (name "unconnected-(P1-Pad17)") (class "Default")
      (node (ref "P1") (pin "17") (pinfunction "17_17") (pintype "passive"))
    )
    (net (code "58") (name "unconnected-(P1-Pad18)") (class "Default")
      (node (ref "P1") (pin "18") (pinfunction "18_18") (pintype "passive"))
    )
    (net (code "59") (name "unconnected-(P1-Pad19)") (class "Default")
      (node (ref "P1") (pin "19") (pinfunction "19_19") (pintype "passive"))
    )
    (net (code "60") (name "unconnected-(P1-Pad20)") (class "Default")
      (node (ref "P1") (pin "20") (pinfunction "20_20") (pintype "passive"))
    )
    (net (code "61") (name "unconnected-(P1-Pad21)") (class "Default")
      (node (ref "P1") (pin "21") (pinfunction "21_21") (pintype "passive"))
    )
    (net (code "62") (name "unconnected-(P1-Pad22)") (class "Default")
      (node (ref "P1") (pin "22") (pinfunction "22_22") (pintype "passive"))
    )
    (net (code "63") (name "unconnected-(P1-Pad23)") (class "Default")
      (node (ref "P1") (pin "23") (pinfunction "23_23") (pintype "passive"))
    )
    (net (code "64") (name "unconnected-(P1-Pad24)") (class "Default")
      (node (ref "P1") (pin "24") (pinfunction "24_24") (pintype "passive"))
    )
    (net (code "65") (name "unconnected-(P1-Pad25)") (class "Default")
      (node (ref "P1") (pin "25") (pinfunction "25_25") (pintype "passive"))
    )
    (net (code "66") (name "unconnected-(P1-Pad26)") (class "Default")
      (node (ref "P1") (pin "26") (pinfunction "26_26") (pintype "passive"))
    )
    (net (code "67") (name "unconnected-(P1-Pad27)") (class "Default")
      (node (ref "P1") (pin "27") (pinfunction "27_27") (pintype "passive"))
    )
    (net (code "68") (name "unconnected-(P1-Pad28)") (class "Default")
      (node (ref "P1") (pin "28") (pinfunction "28_28") (pintype "passive"))
    )
    (net (code "69") (name "unconnected-(P1-Pad29)") (class "Default")
      (node (ref "P1") (pin "29") (pinfunction "29_29") (pintype "passive"))
    )
    (net (code "70") (name "unconnected-(P1-Pad30)") (class "Default")
      (node (ref "P1") (pin "30") (pinfunction "30_30") (pintype "passive"))
    )
    (net (code "71") (name "unconnected-(P1-Pad31)") (class "Default")
      (node (ref "P1") (pin "31") (pinfunction "31_31") (pintype "passive"))
    )
    (net (code "72") (name "unconnected-(P1-Pad32)") (class "Default")
      (node (ref "P1") (pin "32") (pinfunction "32_32") (pintype "passive"))
    )
    (net (code "73") (name "unconnected-(P1-Pad33)") (class "Default")
      (node (ref "P1") (pin "33") (pinfunction "33_33") (pintype "passive"))
    )
    (net (code "74") (name "unconnected-(P1-Pad35)") (class "Default")
      (node (ref "P1") (pin "35") (pinfunction "35_35") (pintype "passive"))
    )
    (net (code "75") (name "unconnected-(P1-Pad36)") (class "Default")
      (node (ref "P1") (pin "36") (pinfunction "36_36") (pintype "passive"))
    )
    (net (code "76") (name "unconnected-(P1-Pad37)") (class "Default")
      (node (ref "P1") (pin "37") (pinfunction "37_37") (pintype "passive"))
    )
    (net (code "77") (name "unconnected-(P1-Pad38)") (class "Default")
      (node (ref "P1") (pin "38") (pinfunction "38_38") (pintype "passive"))
    )
    (net (code "78") (name "unconnected-(P1-Pad39)") (class "Default")
      (node (ref "P1") (pin "39") (pinfunction "39_39") (pintype "passive"))
    )
    (net (code "79") (name "unconnected-(P1-Pad40)") (class "Default")
      (node (ref "P1") (pin "40") (pinfunction "40_40") (pintype "passive"))
    )
    (net (code "80") (name "unconnected-(P2-41-Pad1)") (class "Default")
      (node (ref "P2") (pin "1") (pinfunction "41_1") (pintype "passive"))
    )
    (net (code "81") (name "unconnected-(P2-42-Pad2)") (class "Default")
      (node (ref "P2") (pin "2") (pinfunction "42_2") (pintype "passive"))
    )
    (net (code "82") (name "unconnected-(P3-Pad3)") (class "Default")
      (node (ref "P3") (pin "3") (pinfunction "3_3") (pintype "passive"))
    )
    (net (code "83") (name "unconnected-(P3-Pad4)") (class "Default")
      (node (ref "P3") (pin "4") (pinfunction "4_4") (pintype "passive"))
    )
    (net (code "84") (name "unconnected-(P3-Pad5)") (class "Default")
      (node (ref "P3") (pin "5") (pinfunction "5_5") (pintype "passive"))
    )
    (net (code "85") (name "unconnected-(P3-Pad6)") (class "Default")
      (node (ref "P3") (pin "6") (pinfunction "6_6") (pintype "passive"))
    )
    (net (code "86") (name "unconnected-(P3-Pad7)") (class "Default")
      (node (ref "P3") (pin "7") (pinfunction "7_7") (pintype "passive"))
    )
    (net (code "87") (name "unconnected-(P3-Pad11)") (class "Default")
      (node (ref "P3") (pin "11") (pinfunction "11_11") (pintype "passive"))
    )
    (net (code "88") (name "unconnected-(P3-Pad13)") (class "Default")
      (node (ref "P3") (pin "13") (pinfunction "13_13") (pintype "passive"))
    )
    (net (code "89") (name "unconnected-(P3-Pad14)") (class "Default")
      (node (ref "P3") (pin "14") (pinfunction "14_14") (pintype "passive"))
    )
    (net (code "90") (name "unconnected-(P3-Pad15)") (class "Default")
      (node (ref "P3") (pin "15") (pinfunction "15_15") (pintype "passive"))
    )
    (net (code "91") (name "unconnected-(P3-Pad16)") (class "Default")
      (node (ref "P3") (pin "16") (pinfunction "16_16") (pintype "passive"))
    )
    (net (code "92") (name "unconnected-(P3-Pad17)") (class "Default")
      (node (ref "P3") (pin "17") (pinfunction "17_17") (pintype "passive"))
    )
    (net (code "93") (name "unconnected-(P3-Pad18)") (class "Default")
      (node (ref "P3") (pin "18") (pinfunction "18_18") (pintype "passive"))
    )
    (net (code "94") (name "unconnected-(P3-Pad19)") (class "Default")
      (node (ref "P3") (pin "19") (pinfunction "19_19") (pintype "passive"))
    )
    (net (code "95") (name "unconnected-(P3-Pad20)") (class "Default")
      (node (ref "P3") (pin "20") (pinfunction "20_20") (pintype "passive"))
    )
    (net (code "96") (name "unconnected-(P3-Pad21)") (class "Default")
      (node (ref "P3") (pin "21") (pinfunction "21_21") (pintype "passive"))
    )
    (net (code "97") (name "unconnected-(P3-Pad22)") (class "Default")
      (node (ref "P3") (pin "22") (pinfunction "22_22") (pintype "passive"))
    )
    (net (code "98") (name "unconnected-(P3-Pad23)") (class "Default")
      (node (ref "P3") (pin "23") (pinfunction "23_23") (pintype "passive"))
    )
    (net (code "99") (name "unconnected-(P3-Pad24)") (class "Default")
      (node (ref "P3") (pin "24") (pinfunction "24_24") (pintype "passive"))
    )
    (net (code "100") (name "unconnected-(P3-Pad25)") (class "Default")
      (node (ref "P3") (pin "25") (pinfunction "25_25") (pintype "passive"))
    )
    (net (code "101") (name "unconnected-(P3-Pad26)") (class "Default")
      (node (ref "P3") (pin "26") (pinfunction "26_26") (pintype "passive"))
    )
    (net (code "102") (name "unconnected-(P3-Pad27)") (class "Default")
      (node (ref "P3") (pin "27") (pinfunction "27_27") (pintype "passive"))
    )
    (net (code "103") (name "unconnected-(P3-Pad28)") (class "Default")
      (node (ref "P3") (pin "28") (pinfunction "28_28") (pintype "passive"))
    )
    (net (code "104") (name "unconnected-(P3-Pad29)") (class "Default")
      (node (ref "P3") (pin "29") (pinfunction "29_29") (pintype "passive"))
    )
    (net (code "105") (name "unconnected-(P3-Pad30)") (class "Default")
      (node (ref "P3") (pin "30") (pinfunction "30_30") (pintype "passive"))
    )
    (net (code "106") (name "unconnected-(P3-Pad31)") (class "Default")
      (node (ref "P3") (pin "31") (pinfunction "31_31") (pintype "passive"))
    )
    (net (code "107") (name "unconnected-(P3-Pad32)") (class "Default")
      (node (ref "P3") (pin "32") (pinfunction "32_32") (pintype "passive"))
    )
    (net (code "108") (name "unconnected-(P3-Pad33)") (class "Default")
      (node (ref "P3") (pin "33") (pinfunction "33_33") (pintype "passive"))
    )
    (net (code "109") (name "unconnected-(P3-Pad34)") (class "Default")
      (node (ref "P3") (pin "34") (pinfunction "34_34") (pintype "passive"))
    )
    (net (code "110") (name "unconnected-(P3-Pad35)") (class "Default")
      (node (ref "P3") (pin "35") (pinfunction "35_35") (pintype "passive"))
    )
    (net (code "111") (name "unconnected-(P3-Pad36)") (class "Default")
      (node (ref "P3") (pin "36") (pinfunction "36_36") (pintype "passive"))
    )
    (net (code "112") (name "unconnected-(P3-Pad37)") (class "Default")
      (node (ref "P3") (pin "37") (pinfunction "37_37") (pintype "passive"))
    )
    (net (code "113") (name "unconnected-(P3-Pad38)") (class "Default")
      (node (ref "P3") (pin "38") (pinfunction "38_38") (pintype "passive"))
    )
    (net (code "114") (name "unconnected-(P3-Pad39)") (class "Default")
      (node (ref "P3") (pin "39") (pinfunction "39_39") (pintype "passive"))
    )
    (net (code "115") (name "unconnected-(P3-Pad40)") (class "Default")
      (node (ref "P3") (pin "40") (pinfunction "40_40") (pintype "passive"))
    )
    (net (code "116") (name "unconnected-(P4-41-Pad1)") (class "Default")
      (node (ref "P4") (pin "1") (pinfunction "41_1") (pintype "passive"))
    )
    (net (code "117") (name "unconnected-(P4-42-Pad2)") (class "Default")
      (node (ref "P4") (pin "2") (pinfunction "42_2") (pintype "passive"))
    )
    (net (code "118") (name "unconnected-(P4-43-Pad3)") (class "Default")
      (node (ref "P4") (pin "3") (pinfunction "43_3") (pintype "passive"))
    )
    (net (code "119") (name "unconnected-(P4-44-Pad4)") (class "Default")
      (node (ref "P4") (pin "4") (pinfunction "44_4") (pintype "passive"))
    )
    (net (code "120") (name "unconnected-(P4-45-Pad5)") (class "Default")
      (node (ref "P4") (pin "5") (pinfunction "45_5") (pintype "passive"))
    )
    (net (code "121") (name "unconnected-(P4-46-Pad6)") (class "Default")
      (node (ref "P4") (pin "6") (pinfunction "46_6") (pintype "passive"))
    )
    (net (code "122") (name "unconnected-(SIM1-ADC-Pad25)") (class "Default")
      (node (ref "SIM1") (pin "25") (pinfunction "ADC_25") (pintype "passive"))
    )
    (net (code "123") (name "unconnected-(SIM1-CTS-Pad7)") (class "Default")
      (node (ref "SIM1") (pin "7") (pinfunction "CTS_7") (pintype "passive"))
    )
    (net (code "124") (name "unconnected-(SIM1-DCD-Pad5)") (class "Default")
      (node (ref "SIM1") (pin "5") (pinfunction "DCD_5") (pintype "passive"))
    )
    (net (code "125") (name "unconnected-(SIM1-DISP_CLK-Pad11)") (class "Default")
      (node (ref "SIM1") (pin "11") (pinfunction "DISP_CLK_11") (pintype "passive"))
    )
    (net (code "126") (name "unconnected-(SIM1-DISP_CS-Pad14)") (class "Default")
      (node (ref "SIM1") (pin "14") (pinfunction "DISP_CS_14") (pintype "passive"))
    )
    (net (code "127") (name "unconnected-(SIM1-DISP_DATA-Pad12)") (class "Default")
      (node (ref "SIM1") (pin "12") (pinfunction "DISP_DATA_12") (pintype "passive"))
    )
    (net (code "128") (name "unconnected-(SIM1-DISP_D{slash}C-Pad13)") (class "Default")
      (node (ref "SIM1") (pin "13") (pinfunction "DISP_D/C_13") (pintype "passive"))
    )
    (net (code "129") (name "unconnected-(SIM1-DSR-Pad6)") (class "Default")
      (node (ref "SIM1") (pin "6") (pinfunction "DSR_6") (pintype "passive"))
    )
    (net (code "130") (name "unconnected-(SIM1-DTR-Pad3)") (class "Default")
      (node (ref "SIM1") (pin "3") (pinfunction "DTR_3") (pintype "passive"))
    )
    (net (code "131") (name "unconnected-(SIM1-GPIO1-Pad40)") (class "Default")
      (node (ref "SIM1") (pin "40") (pinfunction "GPIO1_40") (pintype "bidirectional"))
    )
    (net (code "132") (name "unconnected-(SIM1-GPIO2-Pad41)") (class "Default")
      (node (ref "SIM1") (pin "41") (pinfunction "GPIO2_41") (pintype "bidirectional"))
    )
    (net (code "133") (name "unconnected-(SIM1-GPIO3-Pad42)") (class "Default")
      (node (ref "SIM1") (pin "42") (pinfunction "GPIO3_42") (pintype "bidirectional"))
    )
    (net (code "134") (name "unconnected-(SIM1-GPIO4-Pad43)") (class "Default")
      (node (ref "SIM1") (pin "43") (pinfunction "GPIO4_43") (pintype "bidirectional"))
    )
    (net (code "135") (name "unconnected-(SIM1-GPIO5-Pad44)") (class "Default")
      (node (ref "SIM1") (pin "44") (pinfunction "GPIO5_44") (pintype "bidirectional"))
    )
    (net (code "136") (name "unconnected-(SIM1-GPIO6-Pad47)") (class "Default")
      (node (ref "SIM1") (pin "47") (pinfunction "GPIO6_47") (pintype "bidirectional"))
    )
    (net (code "137") (name "unconnected-(SIM1-GPIO7-Pad48)") (class "Default")
      (node (ref "SIM1") (pin "48") (pinfunction "GPIO7_48") (pintype "bidirectional"))
    )
    (net (code "138") (name "unconnected-(SIM1-GPIO8-Pad49)") (class "Default")
      (node (ref "SIM1") (pin "49") (pinfunction "GPIO8_49") (pintype "bidirectional"))
    )
    (net (code "139") (name "unconnected-(SIM1-GPIO9-Pad50)") (class "Default")
      (node (ref "SIM1") (pin "50") (pinfunction "GPIO9_50") (pintype "bidirectional"))
    )
    (net (code "140") (name "unconnected-(SIM1-GPIO10-Pad51)") (class "Default")
      (node (ref "SIM1") (pin "51") (pinfunction "GPIO10_51") (pintype "bidirectional"))
    )
    (net (code "141") (name "unconnected-(SIM1-GPIO11-Pad67)") (class "Default")
      (node (ref "SIM1") (pin "67") (pinfunction "GPIO11_67") (pintype "bidirectional"))
    )
    (net (code "142") (name "unconnected-(SIM1-GPIO12-Pad68)") (class "Default")
      (node (ref "SIM1") (pin "68") (pinfunction "GPIO12_68") (pintype "bidirectional"))
    )
    (net (code "143") (name "unconnected-(SIM1-LINEIN_L-Pad24)") (class "Default")
      (node (ref "SIM1") (pin "24") (pinfunction "LINEIN_L_24") (pintype "passive"))
    )
    (net (code "144") (name "unconnected-(SIM1-LINEIN_R-Pad23)") (class "Default")
      (node (ref "SIM1") (pin "23") (pinfunction "LINEIN_R_23") (pintype "passive"))
    )
    (net (code "145") (name "unconnected-(SIM1-NRESET-Pad16)") (class "Default")
      (node (ref "SIM1") (pin "16") (pinfunction "NRESET_16") (pintype "input"))
    )
    (net (code "146") (name "unconnected-(SIM1-PWM1-Pad35)") (class "Default")
      (node (ref "SIM1") (pin "35") (pinfunction "PWM1_35") (pintype "output"))
    )
    (net (code "147") (name "unconnected-(SIM1-PWM2-Pad36)") (class "Default")
      (node (ref "SIM1") (pin "36") (pinfunction "PWM2_36") (pintype "output"))
    )
    (net (code "148") (name "unconnected-(SIM1-PWRKEY_out-Pad2)") (class "Default")
      (node (ref "SIM1") (pin "2") (pinfunction "PWRKEY_out_2") (pintype "output"))
    )
    (net (code "149") (name "unconnected-(SIM1-RI-Pad4)") (class "Default")
      (node (ref "SIM1") (pin "4") (pinfunction "RI_4") (pintype "passive"))
    )
    (net (code "150") (name "unconnected-(SIM1-RTS-Pad8)") (class "Default")
      (node (ref "SIM1") (pin "8") (pinfunction "RTS_8") (pintype "passive"))
    )
    (net (code "151") (name "unconnected-(SIM1-RXD-Pad10)") (class "Default")
      (node (ref "SIM1") (pin "10") (pinfunction "RXD_10") (pintype "input"))
    )
    (net (code "152") (name "unconnected-(SIM1-SCL-Pad38)") (class "Default")
      (node (ref "SIM1") (pin "38") (pinfunction "SCL_38") (pintype "output"))
    )
    (net (code "153") (name "unconnected-(SIM1-SDA-Pad37)") (class "Default")
      (node (ref "SIM1") (pin "37") (pinfunction "SDA_37") (pintype "bidirectional"))
    )
    (net (code "154") (name "unconnected-(SIM1-SIM_PRS-Pad34)") (class "Default")
      (node (ref "SIM1") (pin "34") (pinfunction "SIM_PRS_34") (pintype "passive"))
    )
    (net (code "155") (name "unconnected-(SIM1-STATUS-Pad66)") (class "Default")
      (node (ref "SIM1") (pin "66") (pinfunction "STATUS_66") (pintype "output"))
    )
    (net (code "156") (name "unconnected-(SIM1-TXD-Pad9)") (class "Default")
      (node (ref "SIM1") (pin "9") (pinfunction "TXD_9") (pintype "output"))
    )
    (net (code "157") (name "unconnected-(SIM1-VDD_EXT_2V8-Pad15)") (class "Default")
      (node (ref "SIM1") (pin "15") (pinfunction "VDD_EXT_2V8_15") (pintype "output"))
    )
    (net (code "158") (name "unconnected-(SIM1-VRTC-Pad26)") (class "Default")
      (node (ref "SIM1") (pin "26") (pinfunction "VRTC_26") (pintype "passive"))
    )
    (net (code "159") (name "unconnected-(U2-ISET-Pad10)") (class "Default")
      (node (ref "U2") (pin "10") (pinfunction "ISET_10") (pintype "input"))
    )
    (net (code "160") (name "unconnected-(U2-NC-Pad6)") (class "Default")
      (node (ref "U2") (pin "6") (pinfunction "NC_6") (pintype "passive"))
    )
    (net (code "161") (name "unconnected-(U3-ISET-Pad10)") (class "Default")
      (node (ref "U3") (pin "10") (pinfunction "ISET_10") (pintype "input"))
    )
    (net (code "162") (name "unconnected-(U3-NC-Pad6)") (class "Default")
      (node (ref "U3") (pin "6") (pinfunction "NC_6") (pintype "passive"))
    )
    (net (code "163") (name "unconnected-(U101-TAB-Pad6)") (class "Default")
      (node (ref "U101") (pin "6") (pinfunction "TAB_6") (pintype "power_in"))
    )
    (net (code "164") (name "unconnected-(U101-~{ON}{slash}OFF-Pad5)") (class "Default")
      (node (ref "U101") (pin "5") (pinfunction "~{ON}/OFF_5") (pintype "input"))
    )
  )
)
